# Rose_LanteRn.net
KiCad netlist of a schematic drawn in Altium Designer
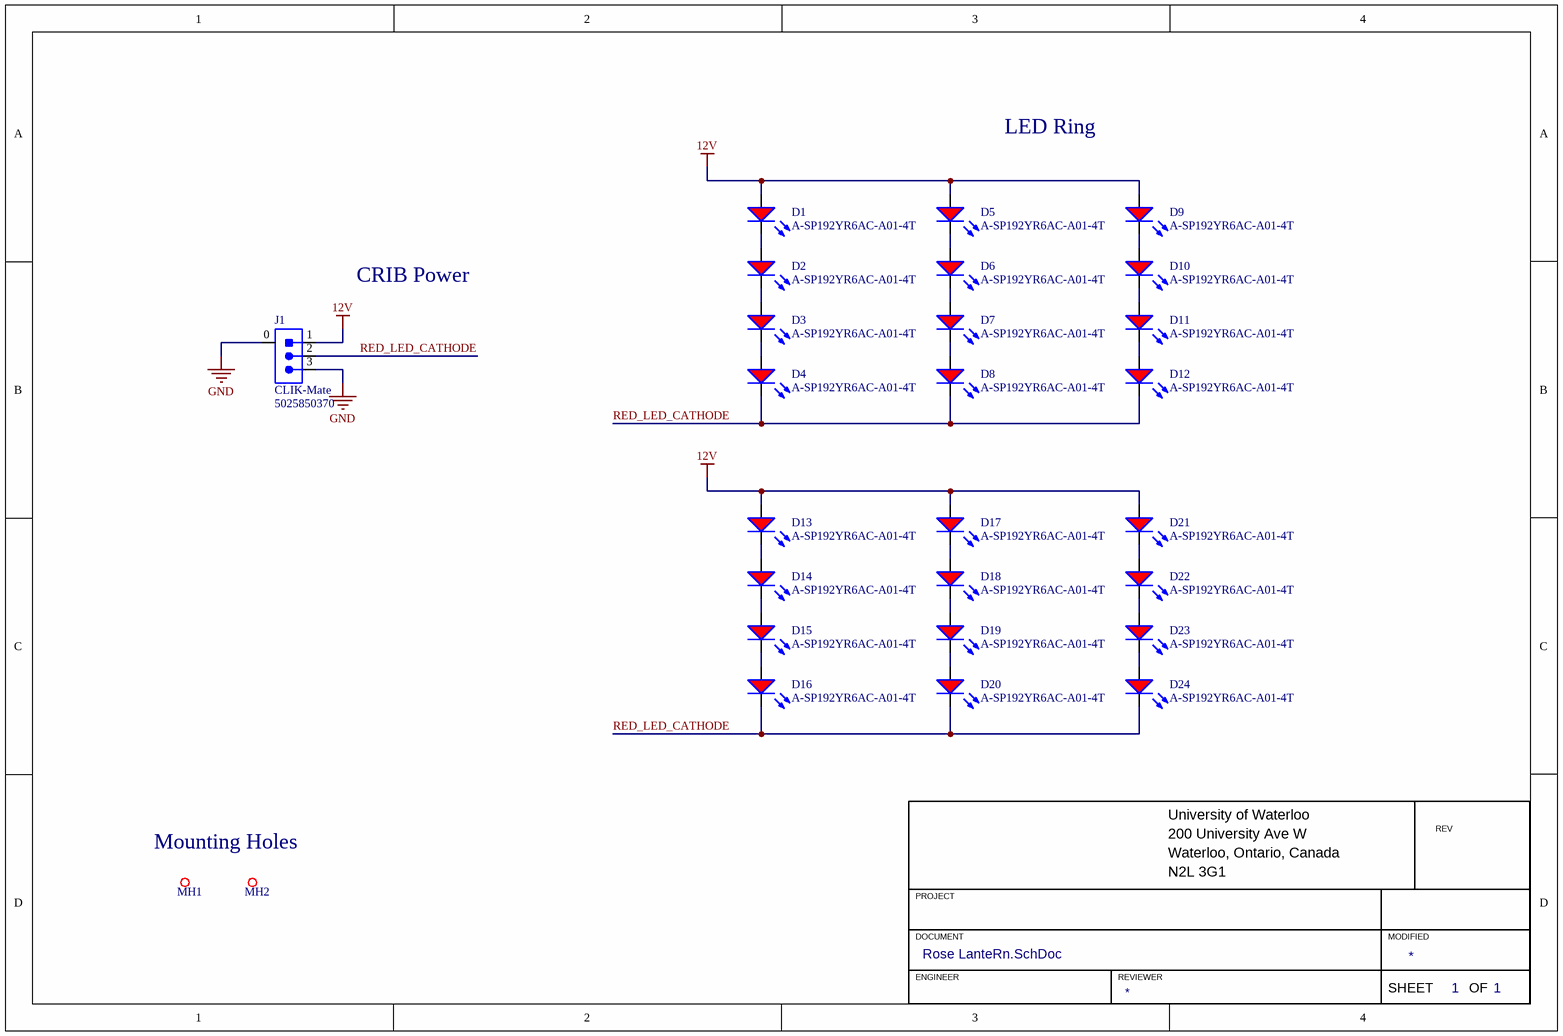
[diagram p0: Rose LanteRn.SchDoc]

(export (version "E")
  (design (tool "Eeschema 10.0.6"))
  (components
    (comp (ref "D1")
      (value "LED_RED_0603")
      (footprint "LED_0603_RED")
      (description "LED RED DIFFUSED 0805 SMD")
      (fields (field (name "MANUFACTURER PART NUMBER 1") "A-SP192YR6AC-A01-4T"))
      (libsource (lib "Personal_Schematic_Library_2022") (part "LED_RED_0603"))
    )
    (comp (ref "D2")
      (value "LED_RED_0603")
      (footprint "LED_0603_RED")
      (description "LED RED DIFFUSED 0805 SMD")
      (fields (field (name "MANUFACTURER PART NUMBER 1") "A-SP192YR6AC-A01-4T"))
      (libsource (lib "Personal_Schematic_Library_2022") (part "LED_RED_0603"))
    )
    (comp (ref "D3")
      (value "LED_RED_0603")
      (footprint "LED_0603_RED")
      (description "LED RED DIFFUSED 0805 SMD")
      (fields (field (name "MANUFACTURER PART NUMBER 1") "A-SP192YR6AC-A01-4T"))
      (libsource (lib "Personal_Schematic_Library_2022") (part "LED_RED_0603"))
    )
    (comp (ref "D4")
      (value "LED_RED_0603")
      (footprint "LED_0603_RED")
      (description "LED RED DIFFUSED 0805 SMD")
      (fields (field (name "MANUFACTURER PART NUMBER 1") "A-SP192YR6AC-A01-4T"))
      (libsource (lib "Personal_Schematic_Library_2022") (part "LED_RED_0603"))
    )
    (comp (ref "D5")
      (value "LED_RED_0603")
      (footprint "LED_0603_RED")
      (description "LED RED DIFFUSED 0805 SMD")
      (fields (field (name "MANUFACTURER PART NUMBER 1") "A-SP192YR6AC-A01-4T"))
      (libsource (lib "Personal_Schematic_Library_2022") (part "LED_RED_0603"))
    )
    (comp (ref "D6")
      (value "LED_RED_0603")
      (footprint "LED_0603_RED")
      (description "LED RED DIFFUSED 0805 SMD")
      (fields (field (name "MANUFACTURER PART NUMBER 1") "A-SP192YR6AC-A01-4T"))
      (libsource (lib "Personal_Schematic_Library_2022") (part "LED_RED_0603"))
    )
    (comp (ref "D7")
      (value "LED_RED_0603")
      (footprint "LED_0603_RED")
      (description "LED RED DIFFUSED 0805 SMD")
      (fields (field (name "MANUFACTURER PART NUMBER 1") "A-SP192YR6AC-A01-4T"))
      (libsource (lib "Personal_Schematic_Library_2022") (part "LED_RED_0603"))
    )
    (comp (ref "D8")
      (value "LED_RED_0603")
      (footprint "LED_0603_RED")
      (description "LED RED DIFFUSED 0805 SMD")
      (fields (field (name "MANUFACTURER PART NUMBER 1") "A-SP192YR6AC-A01-4T"))
      (libsource (lib "Personal_Schematic_Library_2022") (part "LED_RED_0603"))
    )
    (comp (ref "D9")
      (value "LED_RED_0603")
      (footprint "LED_0603_RED")
      (description "LED RED DIFFUSED 0805 SMD")
      (fields (field (name "MANUFACTURER PART NUMBER 1") "A-SP192YR6AC-A01-4T"))
      (libsource (lib "Personal_Schematic_Library_2022") (part "LED_RED_0603"))
    )
    (comp (ref "D10")
      (value "LED_RED_0603")
      (footprint "LED_0603_RED")
      (description "LED RED DIFFUSED 0805 SMD")
      (fields (field (name "MANUFACTURER PART NUMBER 1") "A-SP192YR6AC-A01-4T"))
      (libsource (lib "Personal_Schematic_Library_2022") (part "LED_RED_0603"))
    )
    (comp (ref "D11")
      (value "LED_RED_0603")
      (footprint "LED_0603_RED")
      (description "LED RED DIFFUSED 0805 SMD")
      (fields (field (name "MANUFACTURER PART NUMBER 1") "A-SP192YR6AC-A01-4T"))
      (libsource (lib "Personal_Schematic_Library_2022") (part "LED_RED_0603"))
    )
    (comp (ref "D12")
      (value "LED_RED_0603")
      (footprint "LED_0603_RED")
      (description "LED RED DIFFUSED 0805 SMD")
      (fields (field (name "MANUFACTURER PART NUMBER 1") "A-SP192YR6AC-A01-4T"))
      (libsource (lib "Personal_Schematic_Library_2022") (part "LED_RED_0603"))
    )
    (comp (ref "D13")
      (value "LED_RED_0603")
      (footprint "LED_0603_RED")
      (description "LED RED DIFFUSED 0805 SMD")
      (fields (field (name "MANUFACTURER PART NUMBER 1") "A-SP192YR6AC-A01-4T"))
      (libsource (lib "Personal_Schematic_Library_2022") (part "LED_RED_0603"))
    )
    (comp (ref "D14")
      (value "LED_RED_0603")
      (footprint "LED_0603_RED")
      (description "LED RED DIFFUSED 0805 SMD")
      (fields (field (name "MANUFACTURER PART NUMBER 1") "A-SP192YR6AC-A01-4T"))
      (libsource (lib "Personal_Schematic_Library_2022") (part "LED_RED_0603"))
    )
    (comp (ref "D15")
      (value "LED_RED_0603")
      (footprint "LED_0603_RED")
      (description "LED RED DIFFUSED 0805 SMD")
      (fields (field (name "MANUFACTURER PART NUMBER 1") "A-SP192YR6AC-A01-4T"))
      (libsource (lib "Personal_Schematic_Library_2022") (part "LED_RED_0603"))
    )
    (comp (ref "D16")
      (value "LED_RED_0603")
      (footprint "LED_0603_RED")
      (description "LED RED DIFFUSED 0805 SMD")
      (fields (field (name "MANUFACTURER PART NUMBER 1") "A-SP192YR6AC-A01-4T"))
      (libsource (lib "Personal_Schematic_Library_2022") (part "LED_RED_0603"))
    )
    (comp (ref "D17")
      (value "LED_RED_0603")
      (footprint "LED_0603_RED")
      (description "LED RED DIFFUSED 0805 SMD")
      (fields (field (name "MANUFACTURER PART NUMBER 1") "A-SP192YR6AC-A01-4T"))
      (libsource (lib "Personal_Schematic_Library_2022") (part "LED_RED_0603"))
    )
    (comp (ref "D18")
      (value "LED_RED_0603")
      (footprint "LED_0603_RED")
      (description "LED RED DIFFUSED 0805 SMD")
      (fields (field (name "MANUFACTURER PART NUMBER 1") "A-SP192YR6AC-A01-4T"))
      (libsource (lib "Personal_Schematic_Library_2022") (part "LED_RED_0603"))
    )
    (comp (ref "D19")
      (value "LED_RED_0603")
      (footprint "LED_0603_RED")
      (description "LED RED DIFFUSED 0805 SMD")
      (fields (field (name "MANUFACTURER PART NUMBER 1") "A-SP192YR6AC-A01-4T"))
      (libsource (lib "Personal_Schematic_Library_2022") (part "LED_RED_0603"))
    )
    (comp (ref "D20")
      (value "LED_RED_0603")
      (footprint "LED_0603_RED")
      (description "LED RED DIFFUSED 0805 SMD")
      (fields (field (name "MANUFACTURER PART NUMBER 1") "A-SP192YR6AC-A01-4T"))
      (libsource (lib "Personal_Schematic_Library_2022") (part "LED_RED_0603"))
    )
    (comp (ref "D21")
      (value "LED_RED_0603")
      (footprint "LED_0603_RED")
      (description "LED RED DIFFUSED 0805 SMD")
      (fields (field (name "MANUFACTURER PART NUMBER 1") "A-SP192YR6AC-A01-4T"))
      (libsource (lib "Personal_Schematic_Library_2022") (part "LED_RED_0603"))
    )
    (comp (ref "D22")
      (value "LED_RED_0603")
      (footprint "LED_0603_RED")
      (description "LED RED DIFFUSED 0805 SMD")
      (fields (field (name "MANUFACTURER PART NUMBER 1") "A-SP192YR6AC-A01-4T"))
      (libsource (lib "Personal_Schematic_Library_2022") (part "LED_RED_0603"))
    )
    (comp (ref "D23")
      (value "LED_RED_0603")
      (footprint "LED_0603_RED")
      (description "LED RED DIFFUSED 0805 SMD")
      (fields (field (name "MANUFACTURER PART NUMBER 1") "A-SP192YR6AC-A01-4T"))
      (libsource (lib "Personal_Schematic_Library_2022") (part "LED_RED_0603"))
    )
    (comp (ref "D24")
      (value "LED_RED_0603")
      (footprint "LED_0603_RED")
      (description "LED RED DIFFUSED 0805 SMD")
      (fields (field (name "MANUFACTURER PART NUMBER 1") "A-SP192YR6AC-A01-4T"))
      (libsource (lib "Personal_Schematic_Library_2022") (part "LED_RED_0603"))
    )
    (comp (ref "J1")
      (value "CON_3M_SM_RA")
      (footprint "MOLEX-5025850370")
      (description "CONN RCPT 3POS 0.059 TIN SMD R/A")
      (fields (field (name "FAMILY") "CLIK-Mate") (field (name "MANUFACTURER PART NUMBER 1") "5025850370"))
      (libsource (lib "Personal_Schematic_Library_2022") (part "CON_3M_SM_RA"))
    )
    (comp (ref "MH1")
      (value "MOUNTING_HOLE_M3")
      (footprint "MOUNTING_HOLE_3mm")
      (libsource (lib "UWRT_Schematic_Library_2020") (part "MOUNTING_HOLE_M3"))
    )
    (comp (ref "MH2")
      (value "MOUNTING_HOLE_M3")
      (footprint "MOUNTING_HOLE_3mm")
      (libsource (lib "UWRT_Schematic_Library_2020") (part "MOUNTING_HOLE_M3"))
    )
  )
  (nets
    (net (code "1") (name "/RED_LED_CATHODE") (class "Default")
      (node (ref "D12") (pin "1") (pinfunction "K_1") (pintype "passive"))
      (node (ref "D16") (pin "1") (pinfunction "K_1") (pintype "passive"))
      (node (ref "D20") (pin "1") (pinfunction "K_1") (pintype "passive"))
      (node (ref "D24") (pin "1") (pinfunction "K_1") (pintype "passive"))
      (node (ref "D4") (pin "1") (pinfunction "K_1") (pintype "passive"))
      (node (ref "D8") (pin "1") (pinfunction "K_1") (pintype "passive"))
      (node (ref "J1") (pin "2") (pinfunction "2_2") (pintype "passive"))
    )
    (net (code "2") (name "12V") (class "Default")
      (node (ref "D1") (pin "2") (pinfunction "A_2") (pintype "passive"))
      (node (ref "D13") (pin "2") (pinfunction "A_2") (pintype "passive"))
      (node (ref "D17") (pin "2") (pinfunction "A_2") (pintype "passive"))
      (node (ref "D21") (pin "2") (pinfunction "A_2") (pintype "passive"))
      (node (ref "D5") (pin "2") (pinfunction "A_2") (pintype "passive"))
      (node (ref "D9") (pin "2") (pinfunction "A_2") (pintype "passive"))
      (node (ref "J1") (pin "1") (pinfunction "1_1") (pintype "passive"))
    )
    (net (code "3") (name "GND") (class "Default")
      (node (ref "J1") (pin "0") (pinfunction "0_0") (pintype "passive"))
      (node (ref "J1") (pin "3") (pinfunction "3_3") (pintype "passive"))
    )
    (net (code "4") (name "Net-(D1-K)") (class "Default")
      (node (ref "D1") (pin "1") (pinfunction "K_1") (pintype "passive"))
      (node (ref "D2") (pin "2") (pinfunction "A_2") (pintype "passive"))
    )
    (net (code "5") (name "Net-(D2-K)") (class "Default")
      (node (ref "D2") (pin "1") (pinfunction "K_1") (pintype "passive"))
      (node (ref "D3") (pin "2") (pinfunction "A_2") (pintype "passive"))
    )
    (net (code "6") (name "Net-(D3-K)") (class "Default")
      (node (ref "D3") (pin "1") (pinfunction "K_1") (pintype "passive"))
      (node (ref "D4") (pin "2") (pinfunction "A_2") (pintype "passive"))
    )
    (net (code "7") (name "Net-(D5-K)") (class "Default")
      (node (ref "D5") (pin "1") (pinfunction "K_1") (pintype "passive"))
      (node (ref "D6") (pin "2") (pinfunction "A_2") (pintype "passive"))
    )
    (net (code "8") (name "Net-(D6-K)") (class "Default")
      (node (ref "D6") (pin "1") (pinfunction "K_1") (pintype "passive"))
      (node (ref "D7") (pin "2") (pinfunction "A_2") (pintype "passive"))
    )
    (net (code "9") (name "Net-(D7-K)") (class "Default")
      (node (ref "D7") (pin "1") (pinfunction "K_1") (pintype "passive"))
      (node (ref "D8") (pin "2") (pinfunction "A_2") (pintype "passive"))
    )
    (net (code "10") (name "Net-(D10-A)") (class "Default")
      (node (ref "D10") (pin "2") (pinfunction "A_2") (pintype "passive"))
      (node (ref "D9") (pin "1") (pinfunction "K_1") (pintype "passive"))
    )
    (net (code "11") (name "Net-(D10-K)") (class "Default")
      (node (ref "D10") (pin "1") (pinfunction "K_1") (pintype "passive"))
      (node (ref "D11") (pin "2") (pinfunction "A_2") (pintype "passive"))
    )
    (net (code "12") (name "Net-(D11-K)") (class "Default")
      (node (ref "D11") (pin "1") (pinfunction "K_1") (pintype "passive"))
      (node (ref "D12") (pin "2") (pinfunction "A_2") (pintype "passive"))
    )
    (net (code "13") (name "Net-(D13-K)") (class "Default")
      (node (ref "D13") (pin "1") (pinfunction "K_1") (pintype "passive"))
      (node (ref "D14") (pin "2") (pinfunction "A_2") (pintype "passive"))
    )
    (net (code "14") (name "Net-(D14-K)") (class "Default")
      (node (ref "D14") (pin "1") (pinfunction "K_1") (pintype "passive"))
      (node (ref "D15") (pin "2") (pinfunction "A_2") (pintype "passive"))
    )
    (net (code "15") (name "Net-(D15-K)") (class "Default")
      (node (ref "D15") (pin "1") (pinfunction "K_1") (pintype "passive"))
      (node (ref "D16") (pin "2") (pinfunction "A_2") (pintype "passive"))
    )
    (net (code "16") (name "Net-(D17-K)") (class "Default")
      (node (ref "D17") (pin "1") (pinfunction "K_1") (pintype "passive"))
      (node (ref "D18") (pin "2") (pinfunction "A_2") (pintype "passive"))
    )
    (net (code "17") (name "Net-(D18-K)") (class "Default")
      (node (ref "D18") (pin "1") (pinfunction "K_1") (pintype "passive"))
      (node (ref "D19") (pin "2") (pinfunction "A_2") (pintype "passive"))
    )
    (net (code "18") (name "Net-(D19-K)") (class "Default")
      (node (ref "D19") (pin "1") (pinfunction "K_1") (pintype "passive"))
      (node (ref "D20") (pin "2") (pinfunction "A_2") (pintype "passive"))
    )
    (net (code "19") (name "Net-(D21-K)") (class "Default")
      (node (ref "D21") (pin "1") (pinfunction "K_1") (pintype "passive"))
      (node (ref "D22") (pin "2") (pinfunction "A_2") (pintype "passive"))
    )
    (net (code "20") (name "Net-(D22-K)") (class "Default")
      (node (ref "D22") (pin "1") (pinfunction "K_1") (pintype "passive"))
      (node (ref "D23") (pin "2") (pinfunction "A_2") (pintype "passive"))
    )
    (net (code "21") (name "Net-(D23-K)") (class "Default")
      (node (ref "D23") (pin "1") (pinfunction "K_1") (pintype "passive"))
      (node (ref "D24") (pin "2") (pinfunction "A_2") (pintype "passive"))
    )
  )
)
